# Filter2.net
KiCad netlist of a schematic drawn in Altium Designer
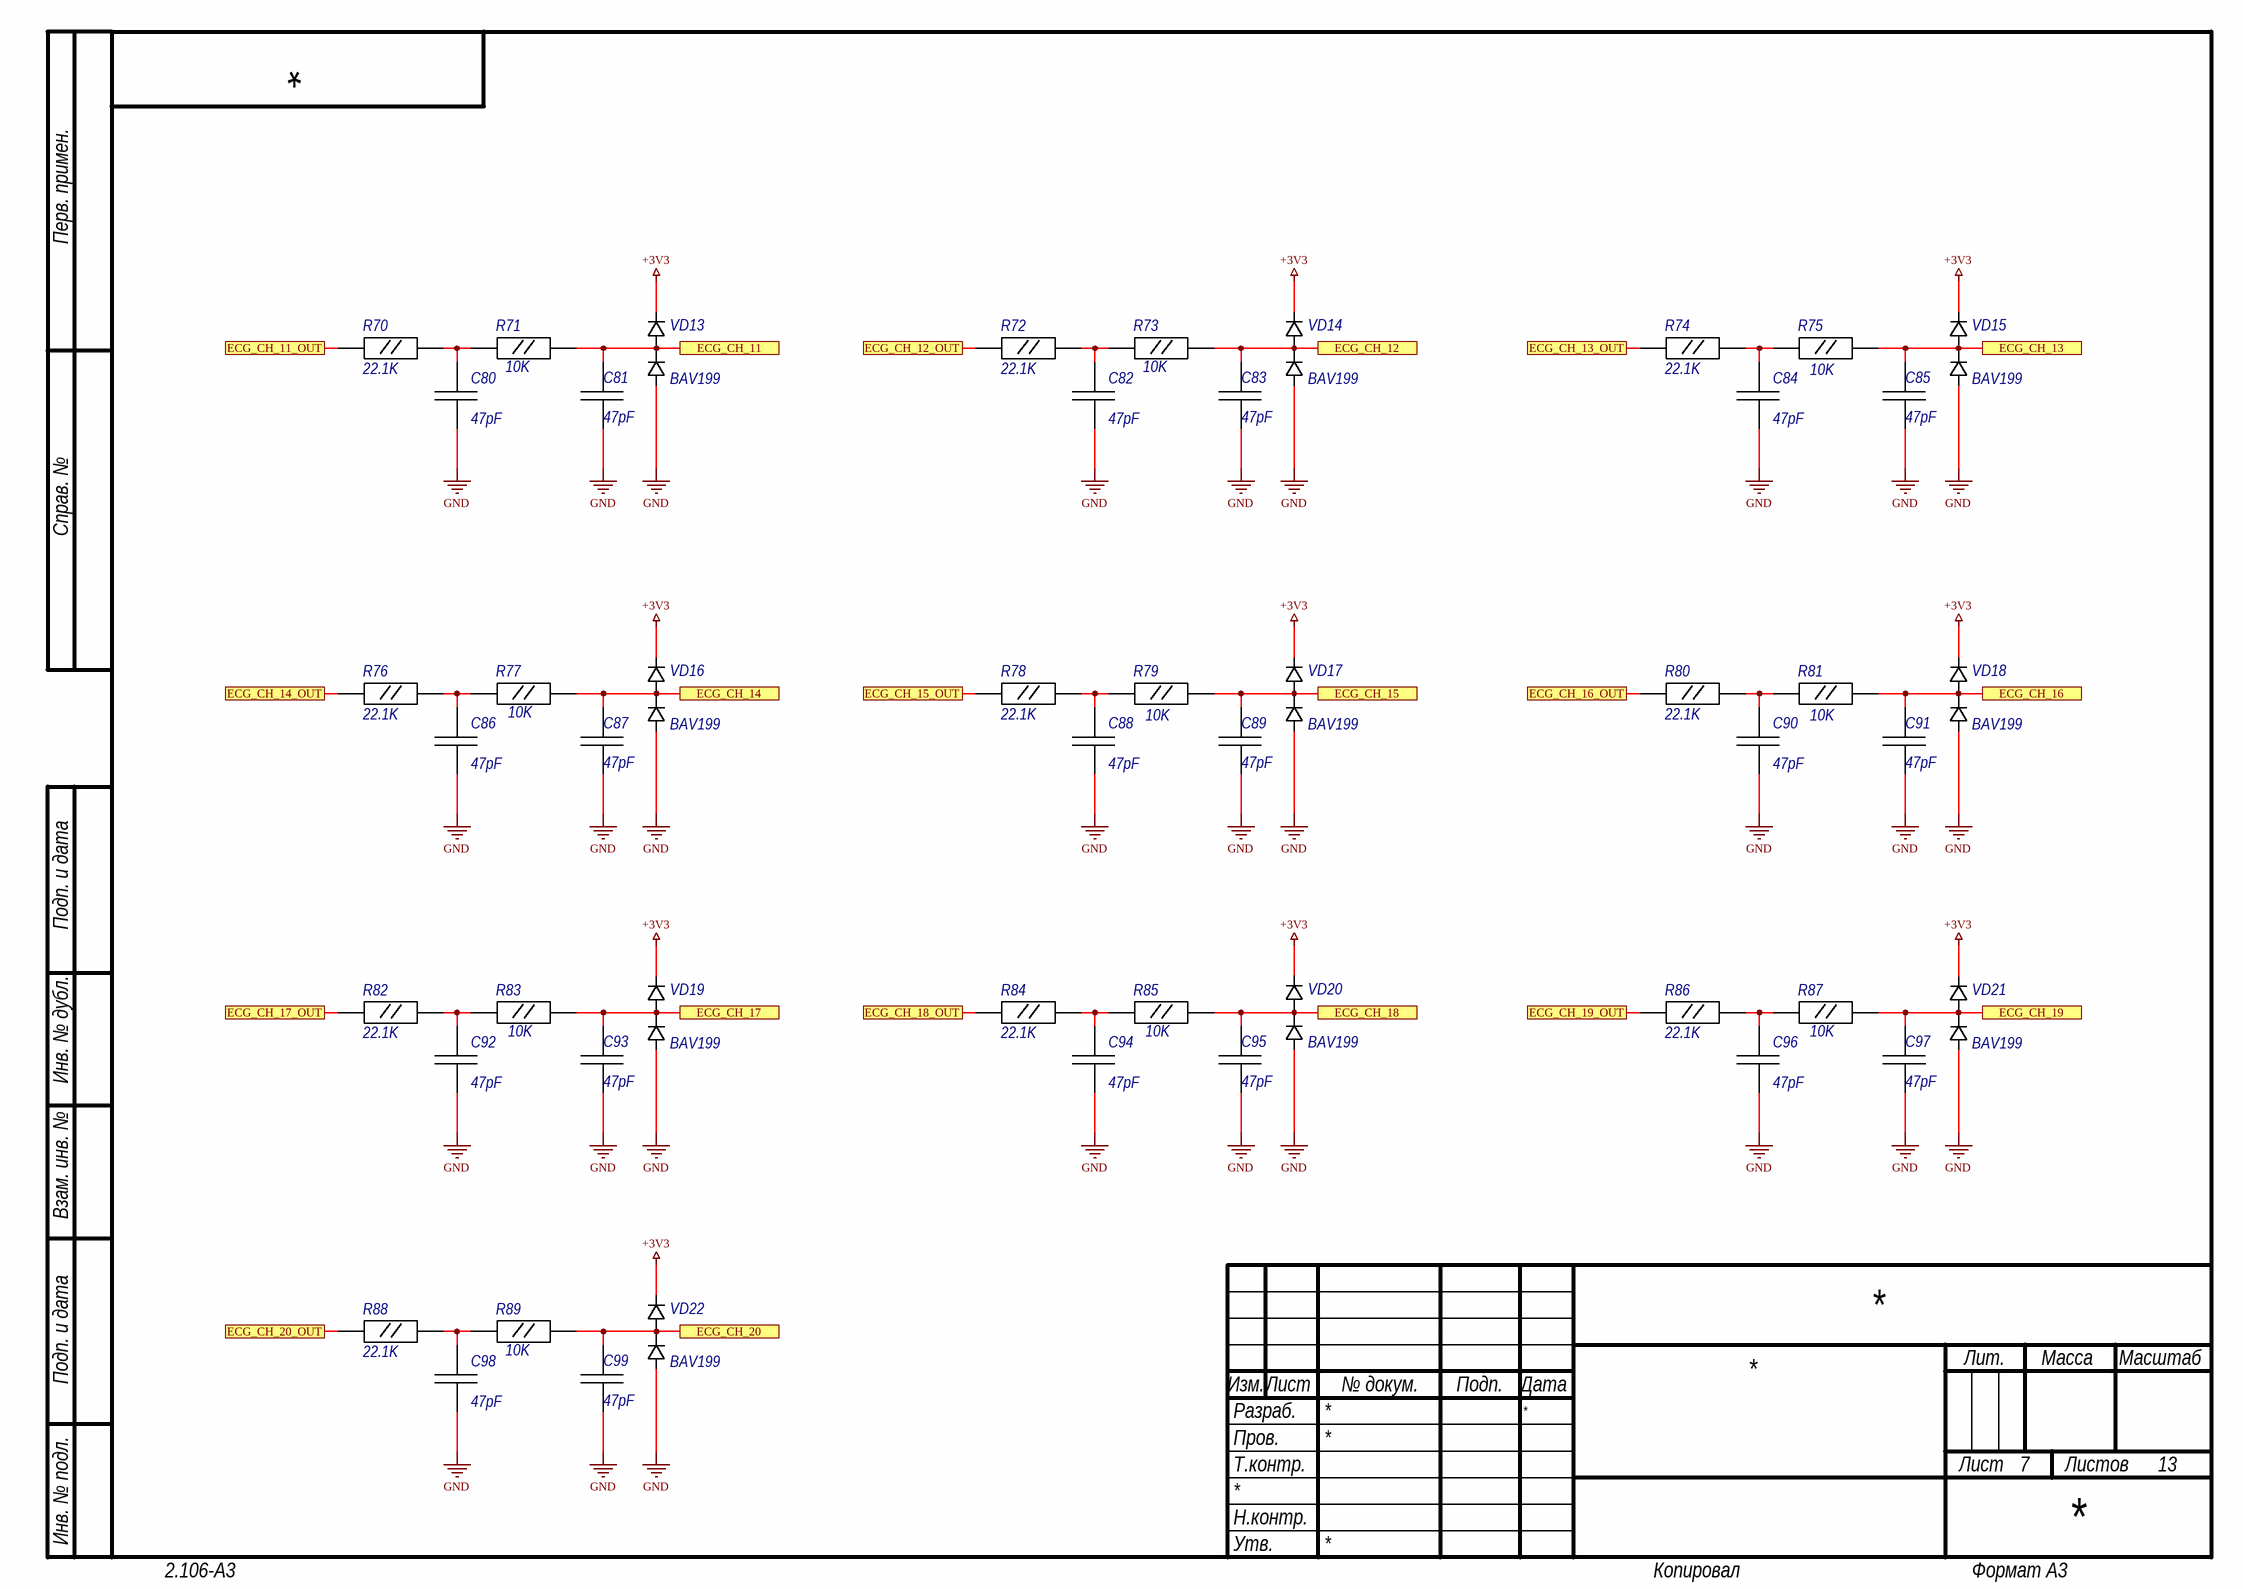
[diagram p0: Filter2.SchDoc]

(export (version "E")
  (design (tool "Eeschema 10.0.6"))
  (components
    (comp (ref "C80")
      (value "47pF")
      (footprint "C0603")
      (description "Ceramic Capacitor SMD")
      (libsource (lib "GOST") (part "CC_SMD_0603"))
    )
    (comp (ref "C81")
      (value "47pF")
      (footprint "C0603")
      (description "Ceramic Capacitor SMD")
      (libsource (lib "GOST") (part "CC_SMD_0603"))
    )
    (comp (ref "C82")
      (value "47pF")
      (footprint "C0603")
      (description "Ceramic Capacitor SMD")
      (libsource (lib "GOST") (part "CC_SMD_0603"))
    )
    (comp (ref "C83")
      (value "47pF")
      (footprint "C0603")
      (description "Ceramic Capacitor SMD")
      (libsource (lib "GOST") (part "CC_SMD_0603"))
    )
    (comp (ref "C84")
      (value "47pF")
      (footprint "C0603")
      (description "Ceramic Capacitor SMD")
      (libsource (lib "GOST") (part "CC_SMD_0603"))
    )
    (comp (ref "C85")
      (value "47pF")
      (footprint "C0603")
      (description "Ceramic Capacitor SMD")
      (libsource (lib "GOST") (part "CC_SMD_0603"))
    )
    (comp (ref "C86")
      (value "47pF")
      (footprint "C0603")
      (description "Ceramic Capacitor SMD")
      (libsource (lib "GOST") (part "CC_SMD_0603"))
    )
    (comp (ref "C87")
      (value "47pF")
      (footprint "C0603")
      (description "Ceramic Capacitor SMD")
      (libsource (lib "GOST") (part "CC_SMD_0603"))
    )
    (comp (ref "C88")
      (value "47pF")
      (footprint "C0603")
      (description "Ceramic Capacitor SMD")
      (libsource (lib "GOST") (part "CC_SMD_0603"))
    )
    (comp (ref "C89")
      (value "47pF")
      (footprint "C0603")
      (description "Ceramic Capacitor SMD")
      (libsource (lib "GOST") (part "CC_SMD_0603"))
    )
    (comp (ref "C90")
      (value "47pF")
      (footprint "C0603")
      (description "Ceramic Capacitor SMD")
      (libsource (lib "GOST") (part "CC_SMD_0603"))
    )
    (comp (ref "C91")
      (value "47pF")
      (footprint "C0603")
      (description "Ceramic Capacitor SMD")
      (libsource (lib "GOST") (part "CC_SMD_0603"))
    )
    (comp (ref "C92")
      (value "47pF")
      (footprint "C0603")
      (description "Ceramic Capacitor SMD")
      (libsource (lib "GOST") (part "CC_SMD_0603"))
    )
    (comp (ref "C93")
      (value "47pF")
      (footprint "C0603")
      (description "Ceramic Capacitor SMD")
      (libsource (lib "GOST") (part "CC_SMD_0603"))
    )
    (comp (ref "C94")
      (value "47pF")
      (footprint "C0603")
      (description "Ceramic Capacitor SMD")
      (libsource (lib "GOST") (part "CC_SMD_0603"))
    )
    (comp (ref "C95")
      (value "47pF")
      (footprint "C0603")
      (description "Ceramic Capacitor SMD")
      (libsource (lib "GOST") (part "CC_SMD_0603"))
    )
    (comp (ref "C96")
      (value "47pF")
      (footprint "C0603")
      (description "Ceramic Capacitor SMD")
      (libsource (lib "GOST") (part "CC_SMD_0603"))
    )
    (comp (ref "C97")
      (value "47pF")
      (footprint "C0603")
      (description "Ceramic Capacitor SMD")
      (libsource (lib "GOST") (part "CC_SMD_0603"))
    )
    (comp (ref "C98")
      (value "47pF")
      (footprint "C0603")
      (description "Ceramic Capacitor SMD")
      (libsource (lib "GOST") (part "CC_SMD_0603"))
    )
    (comp (ref "C99")
      (value "47pF")
      (footprint "C0603")
      (description "Ceramic Capacitor SMD")
      (libsource (lib "GOST") (part "CC_SMD_0603"))
    )
    (comp (ref "R70")
      (value "22.1K")
      (footprint "R0603")
      (description "Resistor SMD")
      (libsource (lib "GOST") (part "R0603"))
    )
    (comp (ref "R71")
      (value "10K")
      (footprint "R0603")
      (description "Resistor SMD")
      (libsource (lib "GOST") (part "R0603"))
    )
    (comp (ref "R72")
      (value "22.1K")
      (footprint "R0603")
      (description "Resistor SMD")
      (libsource (lib "GOST") (part "R0603"))
    )
    (comp (ref "R73")
      (value "10K")
      (footprint "R0603")
      (description "Resistor SMD")
      (libsource (lib "GOST") (part "R0603"))
    )
    (comp (ref "R74")
      (value "22.1K")
      (footprint "R0603")
      (description "Resistor SMD")
      (libsource (lib "GOST") (part "R0603"))
    )
    (comp (ref "R75")
      (value "10K")
      (footprint "R0603")
      (description "Resistor SMD")
      (libsource (lib "GOST") (part "R0603"))
    )
    (comp (ref "R76")
      (value "22.1K")
      (footprint "R0603")
      (description "Resistor SMD")
      (libsource (lib "GOST") (part "R0603"))
    )
    (comp (ref "R77")
      (value "10K")
      (footprint "R0603")
      (description "Resistor SMD")
      (libsource (lib "GOST") (part "R0603"))
    )
    (comp (ref "R78")
      (value "22.1K")
      (footprint "R0603")
      (description "Resistor SMD")
      (libsource (lib "GOST") (part "R0603"))
    )
    (comp (ref "R79")
      (value "10K")
      (footprint "R0603")
      (description "Resistor SMD")
      (libsource (lib "GOST") (part "R0603"))
    )
    (comp (ref "R80")
      (value "22.1K")
      (footprint "R0603")
      (description "Resistor SMD")
      (libsource (lib "GOST") (part "R0603"))
    )
    (comp (ref "R81")
      (value "10K")
      (footprint "R0603")
      (description "Resistor SMD")
      (libsource (lib "GOST") (part "R0603"))
    )
    (comp (ref "R82")
      (value "22.1K")
      (footprint "R0603")
      (description "Resistor SMD")
      (libsource (lib "GOST") (part "R0603"))
    )
    (comp (ref "R83")
      (value "10K")
      (footprint "R0603")
      (description "Resistor SMD")
      (libsource (lib "GOST") (part "R0603"))
    )
    (comp (ref "R84")
      (value "22.1K")
      (footprint "R0603")
      (description "Resistor SMD")
      (libsource (lib "GOST") (part "R0603"))
    )
    (comp (ref "R85")
      (value "10K")
      (footprint "R0603")
      (description "Resistor SMD")
      (libsource (lib "GOST") (part "R0603"))
    )
    (comp (ref "R86")
      (value "22.1K")
      (footprint "R0603")
      (description "Resistor SMD")
      (libsource (lib "GOST") (part "R0603"))
    )
    (comp (ref "R87")
      (value "10K")
      (footprint "R0603")
      (description "Resistor SMD")
      (libsource (lib "GOST") (part "R0603"))
    )
    (comp (ref "R88")
      (value "22.1K")
      (footprint "R0603")
      (description "Resistor SMD")
      (libsource (lib "GOST") (part "R0603"))
    )
    (comp (ref "R89")
      (value "10K")
      (footprint "R0603")
      (description "Resistor SMD")
      (libsource (lib "GOST") (part "R0603"))
    )
    (comp (ref "VD13")
      (value "BAV199")
      (footprint "SOT23")
      (description "Diod Schottky")
      (fields (field (name "MANUFACTURER PART NUMBER 1") "BAV199"))
      (libsource (lib "GOST") (part "DIODE_BAV199"))
    )
    (comp (ref "VD14")
      (value "BAV199")
      (footprint "SOT23")
      (description "Diod Schottky")
      (fields (field (name "MANUFACTURER PART NUMBER 1") "BAV199"))
      (libsource (lib "GOST") (part "DIODE_BAV199"))
    )
    (comp (ref "VD15")
      (value "BAV199")
      (footprint "SOT23")
      (description "Diod Schottky")
      (fields (field (name "MANUFACTURER PART NUMBER 1") "BAV199"))
      (libsource (lib "GOST") (part "DIODE_BAV199"))
    )
    (comp (ref "VD16")
      (value "BAV199")
      (footprint "SOT23")
      (description "Diod Schottky")
      (fields (field (name "MANUFACTURER PART NUMBER 1") "BAV199"))
      (libsource (lib "GOST") (part "DIODE_BAV199"))
    )
    (comp (ref "VD17")
      (value "BAV199")
      (footprint "SOT23")
      (description "Diod Schottky")
      (fields (field (name "MANUFACTURER PART NUMBER 1") "BAV199"))
      (libsource (lib "GOST") (part "DIODE_BAV199"))
    )
    (comp (ref "VD18")
      (value "BAV199")
      (footprint "SOT23")
      (description "Diod Schottky")
      (fields (field (name "MANUFACTURER PART NUMBER 1") "BAV199"))
      (libsource (lib "GOST") (part "DIODE_BAV199"))
    )
    (comp (ref "VD19")
      (value "BAV199")
      (footprint "SOT23")
      (description "Diod Schottky")
      (fields (field (name "MANUFACTURER PART NUMBER 1") "BAV199"))
      (libsource (lib "GOST") (part "DIODE_BAV199"))
    )
    (comp (ref "VD20")
      (value "BAV199")
      (footprint "SOT23")
      (description "Diod Schottky")
      (fields (field (name "MANUFACTURER PART NUMBER 1") "BAV199"))
      (libsource (lib "GOST") (part "DIODE_BAV199"))
    )
    (comp (ref "VD21")
      (value "BAV199")
      (footprint "SOT23")
      (description "Diod Schottky")
      (fields (field (name "MANUFACTURER PART NUMBER 1") "BAV199"))
      (libsource (lib "GOST") (part "DIODE_BAV199"))
    )
    (comp (ref "VD22")
      (value "BAV199")
      (footprint "SOT23")
      (description "Diod Schottky")
      (fields (field (name "MANUFACTURER PART NUMBER 1") "BAV199"))
      (libsource (lib "GOST") (part "DIODE_BAV199"))
    )
  )
  (nets
    (net (code "1") (name "+3V3") (class "Default")
      (node (ref "VD13") (pin "2") (pinfunction "2_2") (pintype "passive"))
      (node (ref "VD14") (pin "2") (pinfunction "2_2") (pintype "passive"))
      (node (ref "VD15") (pin "2") (pinfunction "2_2") (pintype "passive"))
      (node (ref "VD16") (pin "2") (pinfunction "2_2") (pintype "passive"))
      (node (ref "VD17") (pin "2") (pinfunction "2_2") (pintype "passive"))
      (node (ref "VD18") (pin "2") (pinfunction "2_2") (pintype "passive"))
      (node (ref "VD19") (pin "2") (pinfunction "2_2") (pintype "passive"))
      (node (ref "VD20") (pin "2") (pinfunction "2_2") (pintype "passive"))
      (node (ref "VD21") (pin "2") (pinfunction "2_2") (pintype "passive"))
      (node (ref "VD22") (pin "2") (pinfunction "2_2") (pintype "passive"))
    )
    (net (code "2") (name "/ECG_CH_11") (class "Default")
      (node (ref "C81") (pin "2") (pinfunction "2_2") (pintype "passive"))
      (node (ref "R71") (pin "2") (pinfunction "2_2") (pintype "passive"))
      (node (ref "VD13") (pin "3") (pinfunction "3_3") (pintype "passive"))
    )
    (net (code "3") (name "/ECG_CH_11_OUT") (class "Default")
      (node (ref "R70") (pin "1") (pinfunction "1_1") (pintype "passive"))
    )
    (net (code "4") (name "/ECG_CH_12") (class "Default")
      (node (ref "C83") (pin "2") (pinfunction "2_2") (pintype "passive"))
      (node (ref "R73") (pin "2") (pinfunction "2_2") (pintype "passive"))
      (node (ref "VD14") (pin "3") (pinfunction "3_3") (pintype "passive"))
    )
    (net (code "5") (name "/ECG_CH_12_OUT") (class "Default")
      (node (ref "R72") (pin "1") (pinfunction "1_1") (pintype "passive"))
    )
    (net (code "6") (name "/ECG_CH_13") (class "Default")
      (node (ref "C85") (pin "2") (pinfunction "2_2") (pintype "passive"))
      (node (ref "R75") (pin "2") (pinfunction "2_2") (pintype "passive"))
      (node (ref "VD15") (pin "3") (pinfunction "3_3") (pintype "passive"))
    )
    (net (code "7") (name "/ECG_CH_13_OUT") (class "Default")
      (node (ref "R74") (pin "1") (pinfunction "1_1") (pintype "passive"))
    )
    (net (code "8") (name "/ECG_CH_14") (class "Default")
      (node (ref "C87") (pin "2") (pinfunction "2_2") (pintype "passive"))
      (node (ref "R77") (pin "2") (pinfunction "2_2") (pintype "passive"))
      (node (ref "VD16") (pin "3") (pinfunction "3_3") (pintype "passive"))
    )
    (net (code "9") (name "/ECG_CH_14_OUT") (class "Default")
      (node (ref "R76") (pin "1") (pinfunction "1_1") (pintype "passive"))
    )
    (net (code "10") (name "/ECG_CH_15") (class "Default")
      (node (ref "C89") (pin "2") (pinfunction "2_2") (pintype "passive"))
      (node (ref "R79") (pin "2") (pinfunction "2_2") (pintype "passive"))
      (node (ref "VD17") (pin "3") (pinfunction "3_3") (pintype "passive"))
    )
    (net (code "11") (name "/ECG_CH_15_OUT") (class "Default")
      (node (ref "R78") (pin "1") (pinfunction "1_1") (pintype "passive"))
    )
    (net (code "12") (name "/ECG_CH_16") (class "Default")
      (node (ref "C91") (pin "2") (pinfunction "2_2") (pintype "passive"))
      (node (ref "R81") (pin "2") (pinfunction "2_2") (pintype "passive"))
      (node (ref "VD18") (pin "3") (pinfunction "3_3") (pintype "passive"))
    )
    (net (code "13") (name "/ECG_CH_16_OUT") (class "Default")
      (node (ref "R80") (pin "1") (pinfunction "1_1") (pintype "passive"))
    )
    (net (code "14") (name "/ECG_CH_17") (class "Default")
      (node (ref "C93") (pin "2") (pinfunction "2_2") (pintype "passive"))
      (node (ref "R83") (pin "2") (pinfunction "2_2") (pintype "passive"))
      (node (ref "VD19") (pin "3") (pinfunction "3_3") (pintype "passive"))
    )
    (net (code "15") (name "/ECG_CH_17_OUT") (class "Default")
      (node (ref "R82") (pin "1") (pinfunction "1_1") (pintype "passive"))
    )
    (net (code "16") (name "/ECG_CH_18") (class "Default")
      (node (ref "C95") (pin "2") (pinfunction "2_2") (pintype "passive"))
      (node (ref "R85") (pin "2") (pinfunction "2_2") (pintype "passive"))
      (node (ref "VD20") (pin "3") (pinfunction "3_3") (pintype "passive"))
    )
    (net (code "17") (name "/ECG_CH_18_OUT") (class "Default")
      (node (ref "R84") (pin "1") (pinfunction "1_1") (pintype "passive"))
    )
    (net (code "18") (name "/ECG_CH_19") (class "Default")
      (node (ref "C97") (pin "2") (pinfunction "2_2") (pintype "passive"))
      (node (ref "R87") (pin "2") (pinfunction "2_2") (pintype "passive"))
      (node (ref "VD21") (pin "3") (pinfunction "3_3") (pintype "passive"))
    )
    (net (code "19") (name "/ECG_CH_19_OUT") (class "Default")
      (node (ref "R86") (pin "1") (pinfunction "1_1") (pintype "passive"))
    )
    (net (code "20") (name "/ECG_CH_20") (class "Default")
      (node (ref "C99") (pin "2") (pinfunction "2_2") (pintype "passive"))
      (node (ref "R89") (pin "2") (pinfunction "2_2") (pintype "passive"))
      (node (ref "VD22") (pin "3") (pinfunction "3_3") (pintype "passive"))
    )
    (net (code "21") (name "/ECG_CH_20_OUT") (class "Default")
      (node (ref "R88") (pin "1") (pinfunction "1_1") (pintype "passive"))
    )
    (net (code "22") (name "GND") (class "Default")
      (node (ref "C80") (pin "1") (pinfunction "1_1") (pintype "passive"))
      (node (ref "C81") (pin "1") (pinfunction "1_1") (pintype "passive"))
      (node (ref "C82") (pin "1") (pinfunction "1_1") (pintype "passive"))
      (node (ref "C83") (pin "1") (pinfunction "1_1") (pintype "passive"))
      (node (ref "C84") (pin "1") (pinfunction "1_1") (pintype "passive"))
      (node (ref "C85") (pin "1") (pinfunction "1_1") (pintype "passive"))
      (node (ref "C86") (pin "1") (pinfunction "1_1") (pintype "passive"))
      (node (ref "C87") (pin "1") (pinfunction "1_1") (pintype "passive"))
      (node (ref "C88") (pin "1") (pinfunction "1_1") (pintype "passive"))
      (node (ref "C89") (pin "1") (pinfunction "1_1") (pintype "passive"))
      (node (ref "C90") (pin "1") (pinfunction "1_1") (pintype "passive"))
      (node (ref "C91") (pin "1") (pinfunction "1_1") (pintype "passive"))
      (node (ref "C92") (pin "1") (pinfunction "1_1") (pintype "passive"))
      (node (ref "C93") (pin "1") (pinfunction "1_1") (pintype "passive"))
      (node (ref "C94") (pin "1") (pinfunction "1_1") (pintype "passive"))
      (node (ref "C95") (pin "1") (pinfunction "1_1") (pintype "passive"))
      (node (ref "C96") (pin "1") (pinfunction "1_1") (pintype "passive"))
      (node (ref "C97") (pin "1") (pinfunction "1_1") (pintype "passive"))
      (node (ref "C98") (pin "1") (pinfunction "1_1") (pintype "passive"))
      (node (ref "C99") (pin "1") (pinfunction "1_1") (pintype "passive"))
      (node (ref "VD13") (pin "1") (pinfunction "1_1") (pintype "passive"))
      (node (ref "VD14") (pin "1") (pinfunction "1_1") (pintype "passive"))
      (node (ref "VD15") (pin "1") (pinfunction "1_1") (pintype "passive"))
      (node (ref "VD16") (pin "1") (pinfunction "1_1") (pintype "passive"))
      (node (ref "VD17") (pin "1") (pinfunction "1_1") (pintype "passive"))
      (node (ref "VD18") (pin "1") (pinfunction "1_1") (pintype "passive"))
      (node (ref "VD19") (pin "1") (pinfunction "1_1") (pintype "passive"))
      (node (ref "VD20") (pin "1") (pinfunction "1_1") (pintype "passive"))
      (node (ref "VD21") (pin "1") (pinfunction "1_1") (pintype "passive"))
      (node (ref "VD22") (pin "1") (pinfunction "1_1") (pintype "passive"))
    )
    (net (code "23") (name "Net-(C80-Pad2)") (class "Default")
      (node (ref "C80") (pin "2") (pinfunction "2_2") (pintype "passive"))
      (node (ref "R70") (pin "2") (pinfunction "2_2") (pintype "passive"))
      (node (ref "R71") (pin "1") (pinfunction "1_1") (pintype "passive"))
    )
    (net (code "24") (name "Net-(C82-Pad2)") (class "Default")
      (node (ref "C82") (pin "2") (pinfunction "2_2") (pintype "passive"))
      (node (ref "R72") (pin "2") (pinfunction "2_2") (pintype "passive"))
      (node (ref "R73") (pin "1") (pinfunction "1_1") (pintype "passive"))
    )
    (net (code "25") (name "Net-(C84-Pad2)") (class "Default")
      (node (ref "C84") (pin "2") (pinfunction "2_2") (pintype "passive"))
      (node (ref "R74") (pin "2") (pinfunction "2_2") (pintype "passive"))
      (node (ref "R75") (pin "1") (pinfunction "1_1") (pintype "passive"))
    )
    (net (code "26") (name "Net-(C86-Pad2)") (class "Default")
      (node (ref "C86") (pin "2") (pinfunction "2_2") (pintype "passive"))
      (node (ref "R76") (pin "2") (pinfunction "2_2") (pintype "passive"))
      (node (ref "R77") (pin "1") (pinfunction "1_1") (pintype "passive"))
    )
    (net (code "27") (name "Net-(C88-Pad2)") (class "Default")
      (node (ref "C88") (pin "2") (pinfunction "2_2") (pintype "passive"))
      (node (ref "R78") (pin "2") (pinfunction "2_2") (pintype "passive"))
      (node (ref "R79") (pin "1") (pinfunction "1_1") (pintype "passive"))
    )
    (net (code "28") (name "Net-(C90-Pad2)") (class "Default")
      (node (ref "C90") (pin "2") (pinfunction "2_2") (pintype "passive"))
      (node (ref "R80") (pin "2") (pinfunction "2_2") (pintype "passive"))
      (node (ref "R81") (pin "1") (pinfunction "1_1") (pintype "passive"))
    )
    (net (code "29") (name "Net-(C92-Pad2)") (class "Default")
      (node (ref "C92") (pin "2") (pinfunction "2_2") (pintype "passive"))
      (node (ref "R82") (pin "2") (pinfunction "2_2") (pintype "passive"))
      (node (ref "R83") (pin "1") (pinfunction "1_1") (pintype "passive"))
    )
    (net (code "30") (name "Net-(C94-Pad2)") (class "Default")
      (node (ref "C94") (pin "2") (pinfunction "2_2") (pintype "passive"))
      (node (ref "R84") (pin "2") (pinfunction "2_2") (pintype "passive"))
      (node (ref "R85") (pin "1") (pinfunction "1_1") (pintype "passive"))
    )
    (net (code "31") (name "Net-(C96-Pad2)") (class "Default")
      (node (ref "C96") (pin "2") (pinfunction "2_2") (pintype "passive"))
      (node (ref "R86") (pin "2") (pinfunction "2_2") (pintype "passive"))
      (node (ref "R87") (pin "1") (pinfunction "1_1") (pintype "passive"))
    )
    (net (code "32") (name "Net-(C98-Pad2)") (class "Default")
      (node (ref "C98") (pin "2") (pinfunction "2_2") (pintype "passive"))
      (node (ref "R88") (pin "2") (pinfunction "2_2") (pintype "passive"))
      (node (ref "R89") (pin "1") (pinfunction "1_1") (pintype "passive"))
    )
  )
)
